# tvbgone3.net
KiCad netlist of a schematic drawn in EAGLE
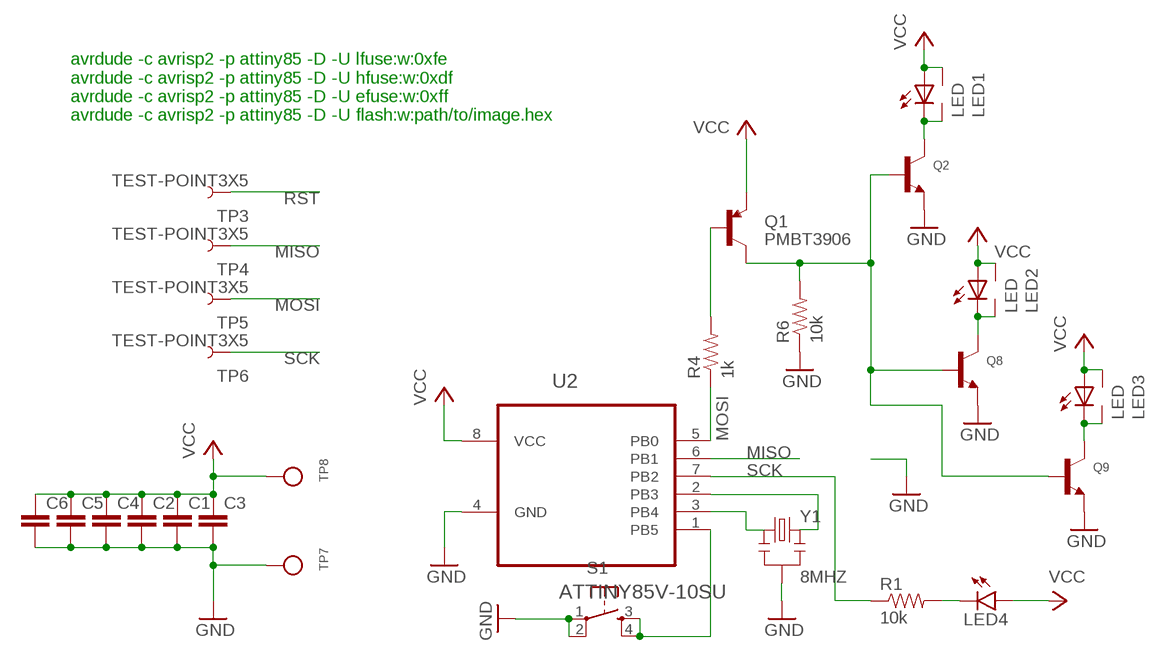
[diagram p0: schematic, sheet 1]

(export (version "E")
  (design (tool "Eeschema 10.0.6"))
  (components
    (comp (ref "C1")
      (value "CAP0603-CAP")
      (footprint "eagle-import:0603-CAP")
      (libsource (lib "eagle-import") (part "CAP0603-CAP"))
    )
    (comp (ref "C2")
      (value "CAP0603-CAP")
      (footprint "eagle-import:0603-CAP")
      (libsource (lib "eagle-import") (part "CAP0603-CAP"))
    )
    (comp (ref "C3")
      (value "CAP0603-CAP")
      (footprint "eagle-import:0603-CAP")
      (libsource (lib "eagle-import") (part "CAP0603-CAP"))
    )
    (comp (ref "C4")
      (value "CAP0603-CAP")
      (footprint "eagle-import:0603-CAP")
      (libsource (lib "eagle-import") (part "CAP0603-CAP"))
    )
    (comp (ref "C5")
      (value "CAP0603-CAP")
      (footprint "eagle-import:0603-CAP")
      (libsource (lib "eagle-import") (part "CAP0603-CAP"))
    )
    (comp (ref "C6")
      (value "CAP0603-CAP")
      (footprint "eagle-import:0603-CAP")
      (libsource (lib "eagle-import") (part "CAP0603-CAP"))
    )
    (comp (ref "LED1")
      (value "LED")
      (footprint "eagle-import:5MM-SIDE")
      (libsource (lib "eagle-import") (part "LED"))
    )
    (comp (ref "LED2")
      (value "LED")
      (footprint "eagle-import:5MM-SIDE")
      (libsource (lib "eagle-import") (part "LED"))
    )
    (comp (ref "LED3")
      (value "LED")
      (footprint "eagle-import:5MM-SIDE")
      (libsource (lib "eagle-import") (part "LED"))
    )
    (comp (ref "LED4")
      (value "LED0603")
      (footprint "eagle-import:LED-0603")
      (libsource (lib "eagle-import") (part "LED0603"))
    )
    (comp (ref "Q1")
      (value "PMBT3906")
      (footprint "eagle-import:SOT23-3")
      (libsource (lib "eagle-import") (part "TRANSISTOR_PNPPMBT3906"))
    )
    (comp (ref "Q2")
      (value "TRANSISTOR_NPN")
      (footprint "eagle-import:SOT-23-R")
      (libsource (lib "eagle-import") (part "TRANSISTOR_NPN"))
    )
    (comp (ref "Q8")
      (value "TRANSISTOR_NPN")
      (footprint "eagle-import:SOT-23-R")
      (libsource (lib "eagle-import") (part "TRANSISTOR_NPN"))
    )
    (comp (ref "Q9")
      (value "TRANSISTOR_NPN")
      (footprint "eagle-import:SOT-23-R")
      (libsource (lib "eagle-import") (part "TRANSISTOR_NPN"))
    )
    (comp (ref "R1")
      (value "10k")
      (footprint "eagle-import:0603-RES")
      (libsource (lib "eagle-import") (part "RESISTOR0603"))
    )
    (comp (ref "R4")
      (value "1k")
      (footprint "eagle-import:0603-RES")
      (libsource (lib "eagle-import") (part "RESISTOR0603"))
    )
    (comp (ref "R6")
      (value "10k")
      (footprint "eagle-import:0603-RES")
      (libsource (lib "eagle-import") (part "RESISTOR0603"))
    )
    (comp (ref "S1")
      (value "TAC_SWITCHSMD")
      (footprint "eagle-import:TACTILE-SWITCH-SMD")
      (libsource (lib "eagle-import") (part "TAC_SWITCHSMD"))
    )
    (comp (ref "TP3")
      (value "TEST-POINT3X5")
      (footprint "eagle-import:PAD.03X.05")
      (libsource (lib "eagle-import") (part "TEST-POINT3X5"))
    )
    (comp (ref "TP4")
      (value "TEST-POINT3X5")
      (footprint "eagle-import:PAD.03X.05")
      (libsource (lib "eagle-import") (part "TEST-POINT3X5"))
    )
    (comp (ref "TP5")
      (value "TEST-POINT3X5")
      (footprint "eagle-import:PAD.03X.05")
      (libsource (lib "eagle-import") (part "TEST-POINT3X5"))
    )
    (comp (ref "TP6")
      (value "TEST-POINT3X5")
      (footprint "eagle-import:PAD.03X.05")
      (libsource (lib "eagle-import") (part "TEST-POINT3X5"))
    )
    (comp (ref "TP7")
      (value "TESTPOINTPAD")
      (footprint "eagle-import:TESTPOINT_PAD_2MM")
      (libsource (lib "eagle-import") (part "TESTPOINTPAD"))
    )
    (comp (ref "TP8")
      (value "TESTPOINTPAD")
      (footprint "eagle-import:TESTPOINT_PAD_2MM")
      (libsource (lib "eagle-import") (part "TESTPOINTPAD"))
    )
    (comp (ref "U2")
      (value "ATTINY85V-10SU")
      (footprint "eagle-import:SOIC127P798X216-8N")
      (libsource (lib "eagle-import") (part "ATTINY85V-10SU"))
    )
    (comp (ref "Y1")
      (value "8MHZ")
      (footprint "eagle-import:RESONATOR-SMD")
      (libsource (lib "eagle-import") (part "RESONATOR8MHZ"))
    )
  )
  (nets
    (net (code "1") (name "/MISO") (class "Default")
      (node (ref "TP4") (pin "P$1") (pinfunction "1_P$1") (pintype "bidirectional"))
      (node (ref "U2") (pin "6") (pinfunction "PB1_6") (pintype "bidirectional"))
    )
    (net (code "2") (name "/MOSI") (class "Default")
      (node (ref "R4") (pin "1") (pinfunction "1_1") (pintype "passive"))
      (node (ref "TP5") (pin "P$1") (pinfunction "1_P$1") (pintype "bidirectional"))
      (node (ref "U2") (pin "5") (pinfunction "PB0_5") (pintype "bidirectional"))
    )
    (net (code "3") (name "/RST") (class "Default")
      (node (ref "S1") (pin "3") (pinfunction "3_3") (pintype "passive"))
      (node (ref "S1") (pin "4") (pinfunction "4_4") (pintype "passive"))
      (node (ref "TP3") (pin "P$1") (pinfunction "1_P$1") (pintype "bidirectional"))
      (node (ref "U2") (pin "1") (pinfunction "PB5_1") (pintype "bidirectional"))
    )
    (net (code "4") (name "/SCK") (class "Default")
      (node (ref "R1") (pin "1") (pinfunction "1_1") (pintype "passive"))
      (node (ref "TP6") (pin "P$1") (pinfunction "1_P$1") (pintype "bidirectional"))
      (node (ref "U2") (pin "7") (pinfunction "PB2_7") (pintype "bidirectional"))
    )
    (net (code "5") (name "GND") (class "Default")
      (node (ref "C1") (pin "2") (pinfunction "2_2") (pintype "passive"))
      (node (ref "C2") (pin "2") (pinfunction "2_2") (pintype "passive"))
      (node (ref "C3") (pin "2") (pinfunction "2_2") (pintype "passive"))
      (node (ref "C4") (pin "2") (pinfunction "2_2") (pintype "passive"))
      (node (ref "C5") (pin "2") (pinfunction "2_2") (pintype "passive"))
      (node (ref "C6") (pin "2") (pinfunction "2_2") (pintype "passive"))
      (node (ref "Q2") (pin "3-EMITTER") (pinfunction "E_3-EMITTER") (pintype "passive"))
      (node (ref "Q8") (pin "3-EMITTER") (pinfunction "E_3-EMITTER") (pintype "passive"))
      (node (ref "Q9") (pin "3-EMITTER") (pinfunction "E_3-EMITTER") (pintype "passive"))
      (node (ref "R6") (pin "1") (pinfunction "1_1") (pintype "passive"))
      (node (ref "S1") (pin "1") (pinfunction "1_1") (pintype "passive"))
      (node (ref "S1") (pin "2") (pinfunction "2_2") (pintype "passive"))
      (node (ref "TP7") (pin "P$1") (pinfunction "P$1_P$1") (pintype "bidirectional"))
      (node (ref "U2") (pin "4") (pinfunction "GND_4") (pintype "passive"))
      (node (ref "Y1") (pin "2") (pinfunction "2_2") (pintype "passive"))
    )
    (net (code "6") (name "Net-(LED1-C)") (class "Default")
      (node (ref "LED1") (pin "K") (pinfunction "C_K") (pintype "passive"))
      (node (ref "LED1") (pin "K2") (pinfunction "C1_K2") (pintype "passive"))
      (node (ref "Q2") (pin "2-COLLECTOR") (pinfunction "C_2-COLLECTOR") (pintype "passive"))
    )
    (net (code "7") (name "Net-(LED2-C)") (class "Default")
      (node (ref "LED2") (pin "K") (pinfunction "C_K") (pintype "passive"))
      (node (ref "LED2") (pin "K2") (pinfunction "C1_K2") (pintype "passive"))
      (node (ref "Q8") (pin "2-COLLECTOR") (pinfunction "C_2-COLLECTOR") (pintype "passive"))
    )
    (net (code "8") (name "Net-(LED3-C)") (class "Default")
      (node (ref "LED3") (pin "K") (pinfunction "C_K") (pintype "passive"))
      (node (ref "LED3") (pin "K2") (pinfunction "C1_K2") (pintype "passive"))
      (node (ref "Q9") (pin "2-COLLECTOR") (pinfunction "C_2-COLLECTOR") (pintype "passive"))
    )
    (net (code "9") (name "Net-(LED4-PadC)") (class "Default")
      (node (ref "LED4") (pin "C") (pinfunction "C_C") (pintype "passive"))
      (node (ref "R1") (pin "2") (pinfunction "2_2") (pintype "passive"))
    )
    (net (code "10") (name "Net-(Q1-B)") (class "Default")
      (node (ref "Q1") (pin "1") (pinfunction "B_1") (pintype "passive"))
      (node (ref "R4") (pin "2") (pinfunction "2_2") (pintype "passive"))
    )
    (net (code "11") (name "Net-(Q1-C)") (class "Default")
      (node (ref "Q1") (pin "3") (pinfunction "C_3") (pintype "passive"))
      (node (ref "Q2") (pin "1-BASE") (pinfunction "B_1-BASE") (pintype "passive"))
      (node (ref "Q8") (pin "1-BASE") (pinfunction "B_1-BASE") (pintype "passive"))
      (node (ref "Q9") (pin "1-BASE") (pinfunction "B_1-BASE") (pintype "passive"))
      (node (ref "R6") (pin "2") (pinfunction "2_2") (pintype "passive"))
    )
    (net (code "12") (name "Net-(U2-PB3)") (class "Default")
      (node (ref "U2") (pin "2") (pinfunction "PB3_2") (pintype "bidirectional"))
      (node (ref "Y1") (pin "3") (pinfunction "3_3") (pintype "passive"))
    )
    (net (code "13") (name "Net-(U2-PB4)") (class "Default")
      (node (ref "U2") (pin "3") (pinfunction "PB4_3") (pintype "bidirectional"))
      (node (ref "Y1") (pin "1") (pinfunction "1_1") (pintype "passive"))
    )
    (net (code "14") (name "VCC") (class "Default")
      (node (ref "C1") (pin "1") (pinfunction "1_1") (pintype "passive"))
      (node (ref "C2") (pin "1") (pinfunction "1_1") (pintype "passive"))
      (node (ref "C3") (pin "1") (pinfunction "1_1") (pintype "passive"))
      (node (ref "C4") (pin "1") (pinfunction "1_1") (pintype "passive"))
      (node (ref "C5") (pin "1") (pinfunction "1_1") (pintype "passive"))
      (node (ref "C6") (pin "1") (pinfunction "1_1") (pintype "passive"))
      (node (ref "LED1") (pin "A") (pinfunction "A_A") (pintype "passive"))
      (node (ref "LED1") (pin "A2") (pinfunction "A1_A2") (pintype "passive"))
      (node (ref "LED2") (pin "A") (pinfunction "A_A") (pintype "passive"))
      (node (ref "LED2") (pin "A2") (pinfunction "A1_A2") (pintype "passive"))
      (node (ref "LED3") (pin "A") (pinfunction "A_A") (pintype "passive"))
      (node (ref "LED3") (pin "A2") (pinfunction "A1_A2") (pintype "passive"))
      (node (ref "LED4") (pin "A") (pinfunction "A_A") (pintype "passive"))
      (node (ref "Q1") (pin "2") (pinfunction "E_2") (pintype "passive"))
      (node (ref "TP8") (pin "P$1") (pinfunction "P$1_P$1") (pintype "bidirectional"))
      (node (ref "U2") (pin "8") (pinfunction "VCC_8") (pintype "power_in"))
    )
  )
)
